# Sensor_Input.net
KiCad netlist of a schematic drawn in Altium Designer
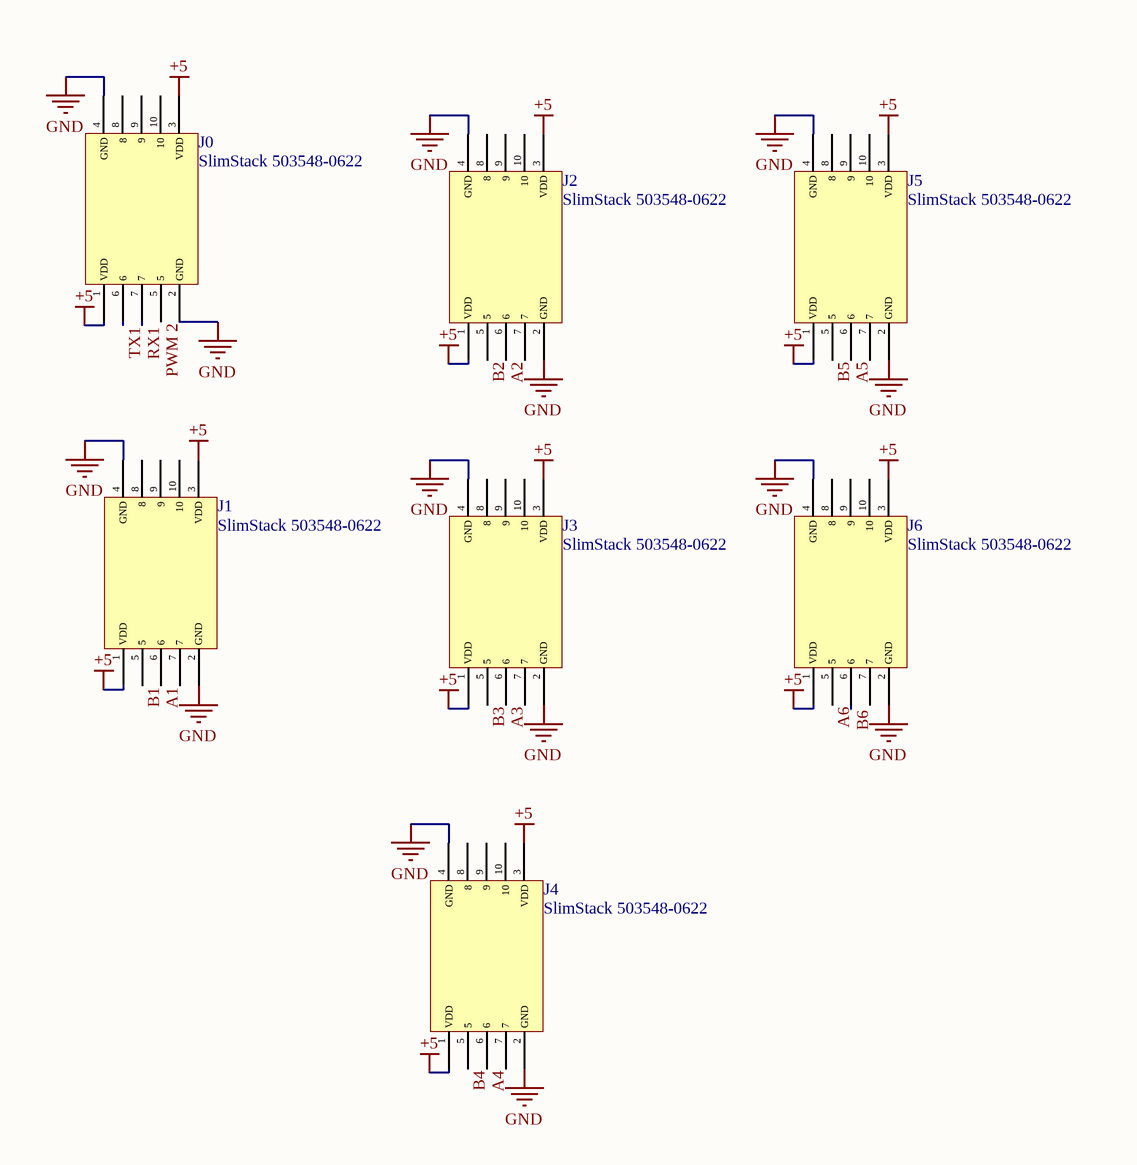
[diagram p0: Sensor Input.SchDoc]

(export (version "E")
  (design (tool "Eeschema 10.0.6"))
  (components
    (comp (ref "J0")
      (value "SlimStack 503548-0622")
      (footprint "SlimStack_503548-0622")
      (libsource (lib "") (part "SlimStack_503548-0622_1"))
    )
    (comp (ref "J1")
      (value "SlimStack 503548-0622")
      (footprint "SlimStack_503548-0622")
      (libsource (lib "SlimStack_503548-0622") (part "SlimStack_503548-0622"))
    )
    (comp (ref "J2")
      (value "SlimStack 503548-0622")
      (footprint "SlimStack_503548-0622")
      (libsource (lib "SlimStack_503548-0622") (part "SlimStack_503548-0622"))
    )
    (comp (ref "J3")
      (value "SlimStack 503548-0622")
      (footprint "SlimStack_503548-0622")
      (libsource (lib "SlimStack_503548-0622") (part "SlimStack_503548-0622"))
    )
    (comp (ref "J4")
      (value "SlimStack 503548-0622")
      (footprint "SlimStack_503548-0622")
      (libsource (lib "SlimStack_503548-0622") (part "SlimStack_503548-0622"))
    )
    (comp (ref "J5")
      (value "SlimStack 503548-0622")
      (footprint "SlimStack_503548-0622")
      (libsource (lib "SlimStack_503548-0622") (part "SlimStack_503548-0622"))
    )
    (comp (ref "J6")
      (value "SlimStack 503548-0622")
      (footprint "SlimStack_503548-0622")
      (libsource (lib "SlimStack_503548-0622") (part "SlimStack_503548-0622"))
    )
  )
  (nets
    (net (code "1") (name "+5") (class "Default")
      (node (ref "J0") (pin "1") (pinfunction "VDD_1") (pintype "passive"))
      (node (ref "J0") (pin "3") (pinfunction "VDD_3") (pintype "passive"))
      (node (ref "J1") (pin "1") (pinfunction "VDD_1") (pintype "passive"))
      (node (ref "J1") (pin "3") (pinfunction "VDD_3") (pintype "passive"))
      (node (ref "J2") (pin "1") (pinfunction "VDD_1") (pintype "passive"))
      (node (ref "J2") (pin "3") (pinfunction "VDD_3") (pintype "passive"))
      (node (ref "J3") (pin "1") (pinfunction "VDD_1") (pintype "passive"))
      (node (ref "J3") (pin "3") (pinfunction "VDD_3") (pintype "passive"))
      (node (ref "J4") (pin "1") (pinfunction "VDD_1") (pintype "passive"))
      (node (ref "J4") (pin "3") (pinfunction "VDD_3") (pintype "passive"))
      (node (ref "J5") (pin "1") (pinfunction "VDD_1") (pintype "passive"))
      (node (ref "J5") (pin "3") (pinfunction "VDD_3") (pintype "passive"))
      (node (ref "J6") (pin "1") (pinfunction "VDD_1") (pintype "passive"))
      (node (ref "J6") (pin "3") (pinfunction "VDD_3") (pintype "passive"))
    )
    (net (code "2") (name "/A1") (class "Default")
      (node (ref "J1") (pin "6") (pinfunction "6_6") (pintype "passive"))
    )
    (net (code "3") (name "/A2") (class "Default")
      (node (ref "J2") (pin "6") (pinfunction "6_6") (pintype "passive"))
    )
    (net (code "4") (name "/A3") (class "Default")
      (node (ref "J3") (pin "6") (pinfunction "6_6") (pintype "passive"))
    )
    (net (code "5") (name "/A4") (class "Default")
      (node (ref "J4") (pin "6") (pinfunction "6_6") (pintype "passive"))
    )
    (net (code "6") (name "/A5") (class "Default")
      (node (ref "J5") (pin "6") (pinfunction "6_6") (pintype "passive"))
    )
    (net (code "7") (name "/A6") (class "Default")
      (node (ref "J6") (pin "5") (pinfunction "5_5") (pintype "passive"))
    )
    (net (code "8") (name "/B1") (class "Default")
      (node (ref "J1") (pin "5") (pinfunction "5_5") (pintype "passive"))
    )
    (net (code "9") (name "/B2") (class "Default")
      (node (ref "J2") (pin "5") (pinfunction "5_5") (pintype "passive"))
    )
    (net (code "10") (name "/B3") (class "Default")
      (node (ref "J3") (pin "5") (pinfunction "5_5") (pintype "passive"))
    )
    (net (code "11") (name "/B4") (class "Default")
      (node (ref "J4") (pin "5") (pinfunction "5_5") (pintype "passive"))
    )
    (net (code "12") (name "/B5") (class "Default")
      (node (ref "J5") (pin "5") (pinfunction "5_5") (pintype "passive"))
    )
    (net (code "13") (name "/B6") (class "Default")
      (node (ref "J6") (pin "6") (pinfunction "6_6") (pintype "passive"))
    )
    (net (code "14") (name "/PWM 2") (class "Default")
      (node (ref "J0") (pin "5") (pinfunction "5_5") (pintype "passive"))
    )
    (net (code "15") (name "/RX1") (class "Default")
      (node (ref "J0") (pin "7") (pinfunction "7_7") (pintype "passive"))
    )
    (net (code "16") (name "/TX1") (class "Default")
      (node (ref "J0") (pin "6") (pinfunction "6_6") (pintype "passive"))
    )
    (net (code "17") (name "GND") (class "Default")
      (node (ref "J0") (pin "2") (pinfunction "GND_2") (pintype "passive"))
      (node (ref "J0") (pin "4") (pinfunction "GND_4") (pintype "passive"))
      (node (ref "J1") (pin "2") (pinfunction "GND_2") (pintype "passive"))
      (node (ref "J1") (pin "4") (pinfunction "GND_4") (pintype "passive"))
      (node (ref "J2") (pin "2") (pinfunction "GND_2") (pintype "passive"))
      (node (ref "J2") (pin "4") (pinfunction "GND_4") (pintype "passive"))
      (node (ref "J3") (pin "2") (pinfunction "GND_2") (pintype "passive"))
      (node (ref "J3") (pin "4") (pinfunction "GND_4") (pintype "passive"))
      (node (ref "J4") (pin "2") (pinfunction "GND_2") (pintype "passive"))
      (node (ref "J4") (pin "4") (pinfunction "GND_4") (pintype "passive"))
      (node (ref "J5") (pin "2") (pinfunction "GND_2") (pintype "passive"))
      (node (ref "J5") (pin "4") (pinfunction "GND_4") (pintype "passive"))
      (node (ref "J6") (pin "2") (pinfunction "GND_2") (pintype "passive"))
      (node (ref "J6") (pin "4") (pinfunction "GND_4") (pintype "passive"))
    )
    (net (code "18") (name "unconnected-(J0-Pad8)") (class "Default")
      (node (ref "J0") (pin "8") (pinfunction "8_8") (pintype "passive"))
    )
    (net (code "19") (name "unconnected-(J0-Pad9)") (class "Default")
      (node (ref "J0") (pin "9") (pinfunction "9_9") (pintype "passive"))
    )
    (net (code "20") (name "unconnected-(J0-Pad10)") (class "Default")
      (node (ref "J0") (pin "10") (pinfunction "10_10") (pintype "passive"))
    )
    (net (code "21") (name "unconnected-(J1-Pad7)") (class "Default")
      (node (ref "J1") (pin "7") (pinfunction "7_7") (pintype "passive"))
    )
    (net (code "22") (name "unconnected-(J1-Pad8)") (class "Default")
      (node (ref "J1") (pin "8") (pinfunction "8_8") (pintype "passive"))
    )
    (net (code "23") (name "unconnected-(J1-Pad9)") (class "Default")
      (node (ref "J1") (pin "9") (pinfunction "9_9") (pintype "passive"))
    )
    (net (code "24") (name "unconnected-(J1-Pad10)") (class "Default")
      (node (ref "J1") (pin "10") (pinfunction "10_10") (pintype "passive"))
    )
    (net (code "25") (name "unconnected-(J2-Pad7)") (class "Default")
      (node (ref "J2") (pin "7") (pinfunction "7_7") (pintype "passive"))
    )
    (net (code "26") (name "unconnected-(J2-Pad8)") (class "Default")
      (node (ref "J2") (pin "8") (pinfunction "8_8") (pintype "passive"))
    )
    (net (code "27") (name "unconnected-(J2-Pad9)") (class "Default")
      (node (ref "J2") (pin "9") (pinfunction "9_9") (pintype "passive"))
    )
    (net (code "28") (name "unconnected-(J2-Pad10)") (class "Default")
      (node (ref "J2") (pin "10") (pinfunction "10_10") (pintype "passive"))
    )
    (net (code "29") (name "unconnected-(J3-Pad7)") (class "Default")
      (node (ref "J3") (pin "7") (pinfunction "7_7") (pintype "passive"))
    )
    (net (code "30") (name "unconnected-(J3-Pad8)") (class "Default")
      (node (ref "J3") (pin "8") (pinfunction "8_8") (pintype "passive"))
    )
    (net (code "31") (name "unconnected-(J3-Pad9)") (class "Default")
      (node (ref "J3") (pin "9") (pinfunction "9_9") (pintype "passive"))
    )
    (net (code "32") (name "unconnected-(J3-Pad10)") (class "Default")
      (node (ref "J3") (pin "10") (pinfunction "10_10") (pintype "passive"))
    )
    (net (code "33") (name "unconnected-(J4-Pad7)") (class "Default")
      (node (ref "J4") (pin "7") (pinfunction "7_7") (pintype "passive"))
    )
    (net (code "34") (name "unconnected-(J4-Pad8)") (class "Default")
      (node (ref "J4") (pin "8") (pinfunction "8_8") (pintype "passive"))
    )
    (net (code "35") (name "unconnected-(J4-Pad9)") (class "Default")
      (node (ref "J4") (pin "9") (pinfunction "9_9") (pintype "passive"))
    )
    (net (code "36") (name "unconnected-(J4-Pad10)") (class "Default")
      (node (ref "J4") (pin "10") (pinfunction "10_10") (pintype "passive"))
    )
    (net (code "37") (name "unconnected-(J5-Pad7)") (class "Default")
      (node (ref "J5") (pin "7") (pinfunction "7_7") (pintype "passive"))
    )
    (net (code "38") (name "unconnected-(J5-Pad8)") (class "Default")
      (node (ref "J5") (pin "8") (pinfunction "8_8") (pintype "passive"))
    )
    (net (code "39") (name "unconnected-(J5-Pad9)") (class "Default")
      (node (ref "J5") (pin "9") (pinfunction "9_9") (pintype "passive"))
    )
    (net (code "40") (name "unconnected-(J5-Pad10)") (class "Default")
      (node (ref "J5") (pin "10") (pinfunction "10_10") (pintype "passive"))
    )
    (net (code "41") (name "unconnected-(J6-Pad7)") (class "Default")
      (node (ref "J6") (pin "7") (pinfunction "7_7") (pintype "passive"))
    )
    (net (code "42") (name "unconnected-(J6-Pad8)") (class "Default")
      (node (ref "J6") (pin "8") (pinfunction "8_8") (pintype "passive"))
    )
    (net (code "43") (name "unconnected-(J6-Pad9)") (class "Default")
      (node (ref "J6") (pin "9") (pinfunction "9_9") (pintype "passive"))
    )
    (net (code "44") (name "unconnected-(J6-Pad10)") (class "Default")
      (node (ref "J6") (pin "10") (pinfunction "10_10") (pintype "passive"))
    )
  )
)
